# Outputs.net
KiCad netlist of a schematic drawn in Altium Designer
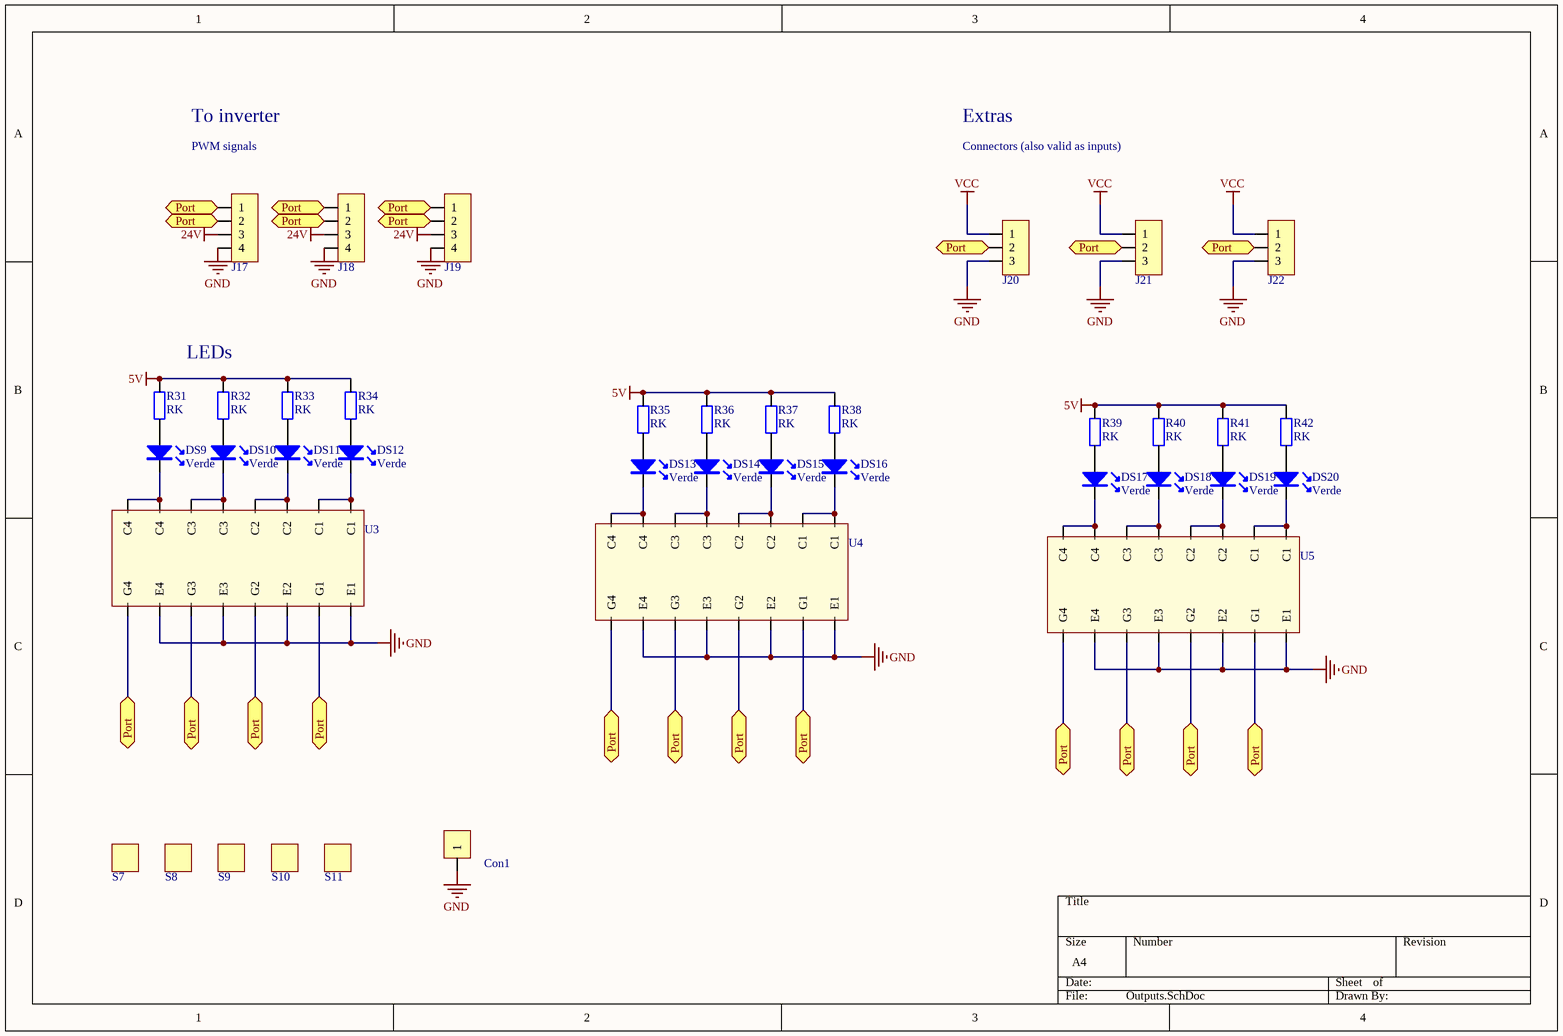
[diagram p0: Outputs.SchDoc]

(export (version "E")
  (design (tool "Eeschema 10.0.6"))
  (components
    (comp (ref "Con1") (value "CON1") (footprint "ShortPad") (libsource (lib "SCH_Lib") (part "CON1")))
    (comp (ref "DS9") (value "Verde") (footprint "Led 3mm") (libsource (lib "SCH_Lib") (part "Led")))
    (comp (ref "DS10") (value "Verde") (footprint "Led 3mm") (libsource (lib "SCH_Lib") (part "Led")))
    (comp (ref "DS11") (value "Verde") (footprint "Led 3mm") (libsource (lib "SCH_Lib") (part "Led")))
    (comp (ref "DS12") (value "Verde") (footprint "Led 3mm") (libsource (lib "SCH_Lib") (part "Led")))
    (comp (ref "DS13") (value "Verde") (footprint "Led 3mm") (libsource (lib "SCH_Lib") (part "Led")))
    (comp (ref "DS14") (value "Verde") (footprint "Led 3mm") (libsource (lib "SCH_Lib") (part "Led")))
    (comp (ref "DS15") (value "Verde") (footprint "Led 3mm") (libsource (lib "SCH_Lib") (part "Led")))
    (comp (ref "DS16") (value "Verde") (footprint "Led 3mm") (libsource (lib "SCH_Lib") (part "Led")))
    (comp (ref "DS17") (value "Verde") (footprint "Led 3mm") (libsource (lib "SCH_Lib") (part "Led")))
    (comp (ref "DS18") (value "Verde") (footprint "Led 3mm") (libsource (lib "SCH_Lib") (part "Led")))
    (comp (ref "DS19") (value "Verde") (footprint "Led 3mm") (libsource (lib "SCH_Lib") (part "Led")))
    (comp (ref "DS20") (value "Verde") (footprint "Led 3mm") (libsource (lib "SCH_Lib") (part "Led")))
    (comp (ref "J17")
      (value "Cleva 2 vias")
      (footprint "Con4_KK_256")
      (libsource (lib "SCH_Lib") (part "Con_4"))
    )
    (comp (ref "J18")
      (value "Cleva 2 vias")
      (footprint "Con4_KK_256")
      (libsource (lib "SCH_Lib") (part "Con_4"))
    )
    (comp (ref "J19")
      (value "Cleva 2 vias")
      (footprint "Con4_KK_256")
      (libsource (lib "SCH_Lib") (part "Con_4"))
    )
    (comp (ref "J20")
      (value "Cleva 2 vias")
      (footprint "Con3_KK_256")
      (libsource (lib "SCH_Lib") (part "Con_3"))
    )
    (comp (ref "J21")
      (value "Cleva 2 vias")
      (footprint "Con3_KK_256")
      (libsource (lib "SCH_Lib") (part "Con_3"))
    )
    (comp (ref "J22")
      (value "Cleva 2 vias")
      (footprint "Con3_KK_256")
      (libsource (lib "SCH_Lib") (part "Con_3"))
    )
    (comp (ref "R31")
      (value "RK")
      (footprint "1206")
      (description "Resistencia")
      (libsource (lib "SCH_Lib") (part "Resistencia"))
    )
    (comp (ref "R32")
      (value "RK")
      (footprint "1206")
      (description "Resistencia")
      (libsource (lib "SCH_Lib") (part "Resistencia"))
    )
    (comp (ref "R33")
      (value "RK")
      (footprint "1206")
      (description "Resistencia")
      (libsource (lib "SCH_Lib") (part "Resistencia"))
    )
    (comp (ref "R34")
      (value "RK")
      (footprint "1206")
      (description "Resistencia")
      (libsource (lib "SCH_Lib") (part "Resistencia"))
    )
    (comp (ref "R35")
      (value "RK")
      (footprint "1206")
      (description "Resistencia")
      (libsource (lib "SCH_Lib") (part "Resistencia"))
    )
    (comp (ref "R36")
      (value "RK")
      (footprint "1206")
      (description "Resistencia")
      (libsource (lib "SCH_Lib") (part "Resistencia"))
    )
    (comp (ref "R37")
      (value "RK")
      (footprint "1206")
      (description "Resistencia")
      (libsource (lib "SCH_Lib") (part "Resistencia"))
    )
    (comp (ref "R38")
      (value "RK")
      (footprint "1206")
      (description "Resistencia")
      (libsource (lib "SCH_Lib") (part "Resistencia"))
    )
    (comp (ref "R39")
      (value "RK")
      (footprint "1206")
      (description "Resistencia")
      (libsource (lib "SCH_Lib") (part "Resistencia"))
    )
    (comp (ref "R40")
      (value "RK")
      (footprint "1206")
      (description "Resistencia")
      (libsource (lib "SCH_Lib") (part "Resistencia"))
    )
    (comp (ref "R41")
      (value "RK")
      (footprint "1206")
      (description "Resistencia")
      (libsource (lib "SCH_Lib") (part "Resistencia"))
    )
    (comp (ref "R42")
      (value "RK")
      (footprint "1206")
      (description "Resistencia")
      (libsource (lib "SCH_Lib") (part "Resistencia"))
    )
    (comp (ref "S7") (value "Support") (footprint "Support") (libsource (lib "SCH_Lib") (part "Support")))
    (comp (ref "S8") (value "Support") (footprint "Support") (libsource (lib "SCH_Lib") (part "Support")))
    (comp (ref "S9") (value "Support") (footprint "Support") (libsource (lib "SCH_Lib") (part "Support")))
    (comp (ref "S10") (value "Support") (footprint "Support") (libsource (lib "SCH_Lib") (part "Support")))
    (comp (ref "S11") (value "Support") (footprint "Support") (libsource (lib "SCH_Lib") (part "Support")))
    (comp (ref "U3") (value "MMPQ3904") (footprint "SO-16") (libsource (lib "SCH_Lib") (part "MMPQ3904")))
    (comp (ref "U4") (value "MMPQ3904") (footprint "SO-16") (libsource (lib "SCH_Lib") (part "MMPQ3904")))
    (comp (ref "U5") (value "MMPQ3904") (footprint "SO-16") (libsource (lib "SCH_Lib") (part "MMPQ3904")))
  )
  (nets
    (net (code "1") (name "/Port") (class "Default")
      (node (ref "J17") (pin "1") (pinfunction "1_1") (pintype "passive"))
      (node (ref "J17") (pin "2") (pinfunction "2_2") (pintype "passive"))
      (node (ref "J18") (pin "1") (pinfunction "1_1") (pintype "passive"))
      (node (ref "J18") (pin "2") (pinfunction "2_2") (pintype "passive"))
      (node (ref "J19") (pin "1") (pinfunction "1_1") (pintype "passive"))
      (node (ref "J19") (pin "2") (pinfunction "2_2") (pintype "passive"))
      (node (ref "J20") (pin "2") (pinfunction "2_2") (pintype "passive"))
      (node (ref "J21") (pin "2") (pinfunction "2_2") (pintype "passive"))
      (node (ref "J22") (pin "2") (pinfunction "2_2") (pintype "passive"))
      (node (ref "U3") (pin "11") (pinfunction "G3_11") (pintype "passive"))
      (node (ref "U3") (pin "13") (pinfunction "G2_13") (pintype "passive"))
      (node (ref "U3") (pin "15") (pinfunction "G1_15") (pintype "passive"))
      (node (ref "U3") (pin "9") (pinfunction "G4_9") (pintype "passive"))
      (node (ref "U4") (pin "11") (pinfunction "G3_11") (pintype "passive"))
      (node (ref "U4") (pin "13") (pinfunction "G2_13") (pintype "passive"))
      (node (ref "U4") (pin "15") (pinfunction "G1_15") (pintype "passive"))
      (node (ref "U4") (pin "9") (pinfunction "G4_9") (pintype "passive"))
      (node (ref "U5") (pin "11") (pinfunction "G3_11") (pintype "passive"))
      (node (ref "U5") (pin "13") (pinfunction "G2_13") (pintype "passive"))
      (node (ref "U5") (pin "15") (pinfunction "G1_15") (pintype "passive"))
      (node (ref "U5") (pin "9") (pinfunction "G4_9") (pintype "passive"))
    )
    (net (code "2") (name "5V") (class "Default")
      (node (ref "R31") (pin "1") (pinfunction "1_1") (pintype "passive"))
      (node (ref "R32") (pin "1") (pinfunction "1_1") (pintype "passive"))
      (node (ref "R33") (pin "1") (pinfunction "1_1") (pintype "passive"))
      (node (ref "R34") (pin "1") (pinfunction "1_1") (pintype "passive"))
      (node (ref "R35") (pin "1") (pinfunction "1_1") (pintype "passive"))
      (node (ref "R36") (pin "1") (pinfunction "1_1") (pintype "passive"))
      (node (ref "R37") (pin "1") (pinfunction "1_1") (pintype "passive"))
      (node (ref "R38") (pin "1") (pinfunction "1_1") (pintype "passive"))
      (node (ref "R39") (pin "1") (pinfunction "1_1") (pintype "passive"))
      (node (ref "R40") (pin "1") (pinfunction "1_1") (pintype "passive"))
      (node (ref "R41") (pin "1") (pinfunction "1_1") (pintype "passive"))
      (node (ref "R42") (pin "1") (pinfunction "1_1") (pintype "passive"))
    )
    (net (code "3") (name "24V") (class "Default")
      (node (ref "J17") (pin "3") (pinfunction "3_3") (pintype "passive"))
      (node (ref "J18") (pin "3") (pinfunction "3_3") (pintype "passive"))
      (node (ref "J19") (pin "3") (pinfunction "3_3") (pintype "passive"))
    )
    (net (code "4") (name "GND") (class "Default")
      (node (ref "Con1") (pin "1") (pinfunction "1_1") (pintype "passive"))
      (node (ref "J17") (pin "4") (pinfunction "4_4") (pintype "passive"))
      (node (ref "J18") (pin "4") (pinfunction "4_4") (pintype "passive"))
      (node (ref "J19") (pin "4") (pinfunction "4_4") (pintype "passive"))
      (node (ref "J20") (pin "3") (pinfunction "3_3") (pintype "passive"))
      (node (ref "J21") (pin "3") (pinfunction "3_3") (pintype "passive"))
      (node (ref "J22") (pin "3") (pinfunction "3_3") (pintype "passive"))
      (node (ref "U3") (pin "10") (pinfunction "E4_10") (pintype "passive"))
      (node (ref "U3") (pin "12") (pinfunction "E3_12") (pintype "passive"))
      (node (ref "U3") (pin "14") (pinfunction "E2_14") (pintype "passive"))
      (node (ref "U3") (pin "16") (pinfunction "E1_16") (pintype "passive"))
      (node (ref "U4") (pin "10") (pinfunction "E4_10") (pintype "passive"))
      (node (ref "U4") (pin "12") (pinfunction "E3_12") (pintype "passive"))
      (node (ref "U4") (pin "14") (pinfunction "E2_14") (pintype "passive"))
      (node (ref "U4") (pin "16") (pinfunction "E1_16") (pintype "passive"))
      (node (ref "U5") (pin "10") (pinfunction "E4_10") (pintype "passive"))
      (node (ref "U5") (pin "12") (pinfunction "E3_12") (pintype "passive"))
      (node (ref "U5") (pin "14") (pinfunction "E2_14") (pintype "passive"))
      (node (ref "U5") (pin "16") (pinfunction "E1_16") (pintype "passive"))
    )
    (net (code "5") (name "Net-(DS9-PadA)") (class "Default")
      (node (ref "DS9") (pin "A") (pinfunction "A_A") (pintype "passive"))
      (node (ref "R31") (pin "2") (pinfunction "2_2") (pintype "passive"))
    )
    (net (code "6") (name "Net-(DS9-PadK)") (class "Default")
      (node (ref "DS9") (pin "K") (pinfunction "K_K") (pintype "passive"))
      (node (ref "U3") (pin "7") (pinfunction "C4_7") (pintype "passive"))
      (node (ref "U3") (pin "8") (pinfunction "C4_8") (pintype "passive"))
    )
    (net (code "7") (name "Net-(DS10-PadA)") (class "Default")
      (node (ref "DS10") (pin "A") (pinfunction "A_A") (pintype "passive"))
      (node (ref "R32") (pin "2") (pinfunction "2_2") (pintype "passive"))
    )
    (net (code "8") (name "Net-(DS10-PadK)") (class "Default")
      (node (ref "DS10") (pin "K") (pinfunction "K_K") (pintype "passive"))
      (node (ref "U3") (pin "5") (pinfunction "C3_5") (pintype "passive"))
      (node (ref "U3") (pin "6") (pinfunction "C3_6") (pintype "passive"))
    )
    (net (code "9") (name "Net-(DS11-PadA)") (class "Default")
      (node (ref "DS11") (pin "A") (pinfunction "A_A") (pintype "passive"))
      (node (ref "R33") (pin "2") (pinfunction "2_2") (pintype "passive"))
    )
    (net (code "10") (name "Net-(DS11-PadK)") (class "Default")
      (node (ref "DS11") (pin "K") (pinfunction "K_K") (pintype "passive"))
      (node (ref "U3") (pin "3") (pinfunction "C2_3") (pintype "passive"))
      (node (ref "U3") (pin "4") (pinfunction "C2_4") (pintype "passive"))
    )
    (net (code "11") (name "Net-(DS12-PadA)") (class "Default")
      (node (ref "DS12") (pin "A") (pinfunction "A_A") (pintype "passive"))
      (node (ref "R34") (pin "2") (pinfunction "2_2") (pintype "passive"))
    )
    (net (code "12") (name "Net-(DS12-PadK)") (class "Default")
      (node (ref "DS12") (pin "K") (pinfunction "K_K") (pintype "passive"))
      (node (ref "U3") (pin "1") (pinfunction "C1_1") (pintype "passive"))
      (node (ref "U3") (pin "2") (pinfunction "C1_2") (pintype "passive"))
    )
    (net (code "13") (name "Net-(DS13-PadA)") (class "Default")
      (node (ref "DS13") (pin "A") (pinfunction "A_A") (pintype "passive"))
      (node (ref "R35") (pin "2") (pinfunction "2_2") (pintype "passive"))
    )
    (net (code "14") (name "Net-(DS13-PadK)") (class "Default")
      (node (ref "DS13") (pin "K") (pinfunction "K_K") (pintype "passive"))
      (node (ref "U4") (pin "7") (pinfunction "C4_7") (pintype "passive"))
      (node (ref "U4") (pin "8") (pinfunction "C4_8") (pintype "passive"))
    )
    (net (code "15") (name "Net-(DS14-PadA)") (class "Default")
      (node (ref "DS14") (pin "A") (pinfunction "A_A") (pintype "passive"))
      (node (ref "R36") (pin "2") (pinfunction "2_2") (pintype "passive"))
    )
    (net (code "16") (name "Net-(DS14-PadK)") (class "Default")
      (node (ref "DS14") (pin "K") (pinfunction "K_K") (pintype "passive"))
      (node (ref "U4") (pin "5") (pinfunction "C3_5") (pintype "passive"))
      (node (ref "U4") (pin "6") (pinfunction "C3_6") (pintype "passive"))
    )
    (net (code "17") (name "Net-(DS15-PadA)") (class "Default")
      (node (ref "DS15") (pin "A") (pinfunction "A_A") (pintype "passive"))
      (node (ref "R37") (pin "2") (pinfunction "2_2") (pintype "passive"))
    )
    (net (code "18") (name "Net-(DS15-PadK)") (class "Default")
      (node (ref "DS15") (pin "K") (pinfunction "K_K") (pintype "passive"))
      (node (ref "U4") (pin "3") (pinfunction "C2_3") (pintype "passive"))
      (node (ref "U4") (pin "4") (pinfunction "C2_4") (pintype "passive"))
    )
    (net (code "19") (name "Net-(DS16-PadA)") (class "Default")
      (node (ref "DS16") (pin "A") (pinfunction "A_A") (pintype "passive"))
      (node (ref "R38") (pin "2") (pinfunction "2_2") (pintype "passive"))
    )
    (net (code "20") (name "Net-(DS16-PadK)") (class "Default")
      (node (ref "DS16") (pin "K") (pinfunction "K_K") (pintype "passive"))
      (node (ref "U4") (pin "1") (pinfunction "C1_1") (pintype "passive"))
      (node (ref "U4") (pin "2") (pinfunction "C1_2") (pintype "passive"))
    )
    (net (code "21") (name "Net-(DS17-PadA)") (class "Default")
      (node (ref "DS17") (pin "A") (pinfunction "A_A") (pintype "passive"))
      (node (ref "R39") (pin "2") (pinfunction "2_2") (pintype "passive"))
    )
    (net (code "22") (name "Net-(DS17-PadK)") (class "Default")
      (node (ref "DS17") (pin "K") (pinfunction "K_K") (pintype "passive"))
      (node (ref "U5") (pin "7") (pinfunction "C4_7") (pintype "passive"))
      (node (ref "U5") (pin "8") (pinfunction "C4_8") (pintype "passive"))
    )
    (net (code "23") (name "Net-(DS18-PadA)") (class "Default")
      (node (ref "DS18") (pin "A") (pinfunction "A_A") (pintype "passive"))
      (node (ref "R40") (pin "2") (pinfunction "2_2") (pintype "passive"))
    )
    (net (code "24") (name "Net-(DS18-PadK)") (class "Default")
      (node (ref "DS18") (pin "K") (pinfunction "K_K") (pintype "passive"))
      (node (ref "U5") (pin "5") (pinfunction "C3_5") (pintype "passive"))
      (node (ref "U5") (pin "6") (pinfunction "C3_6") (pintype "passive"))
    )
    (net (code "25") (name "Net-(DS19-PadA)") (class "Default")
      (node (ref "DS19") (pin "A") (pinfunction "A_A") (pintype "passive"))
      (node (ref "R41") (pin "2") (pinfunction "2_2") (pintype "passive"))
    )
    (net (code "26") (name "Net-(DS19-PadK)") (class "Default")
      (node (ref "DS19") (pin "K") (pinfunction "K_K") (pintype "passive"))
      (node (ref "U5") (pin "3") (pinfunction "C2_3") (pintype "passive"))
      (node (ref "U5") (pin "4") (pinfunction "C2_4") (pintype "passive"))
    )
    (net (code "27") (name "Net-(DS20-PadA)") (class "Default")
      (node (ref "DS20") (pin "A") (pinfunction "A_A") (pintype "passive"))
      (node (ref "R42") (pin "2") (pinfunction "2_2") (pintype "passive"))
    )
    (net (code "28") (name "Net-(DS20-PadK)") (class "Default")
      (node (ref "DS20") (pin "K") (pinfunction "K_K") (pintype "passive"))
      (node (ref "U5") (pin "1") (pinfunction "C1_1") (pintype "passive"))
      (node (ref "U5") (pin "2") (pinfunction "C1_2") (pintype "passive"))
    )
    (net (code "29") (name "VCC") (class "Default")
      (node (ref "J20") (pin "1") (pinfunction "1_1") (pintype "passive"))
      (node (ref "J21") (pin "1") (pinfunction "1_1") (pintype "passive"))
      (node (ref "J22") (pin "1") (pinfunction "1_1") (pintype "passive"))
    )
  )
)
